# lab3_microprocessor.net
KiCad netlist of a schematic drawn in Altium Designer
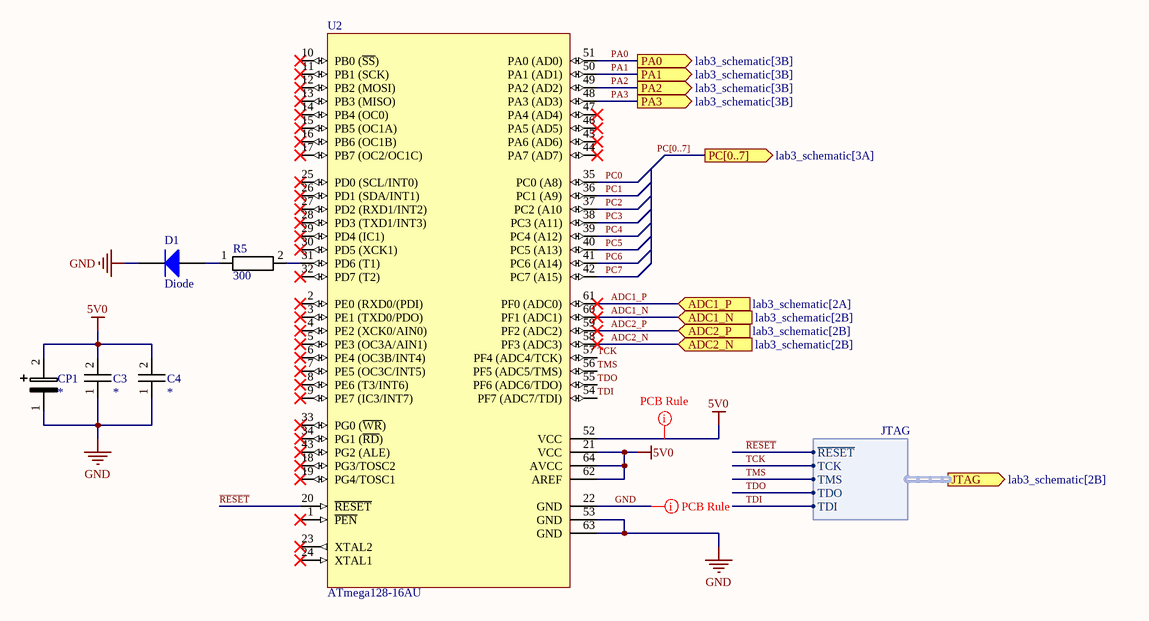
[diagram p0: lab3_microprocessor.SchDoc]

(export (version "E")
  (design (tool "Eeschema 10.0.6"))
  (components
    (comp (ref "C3")
      (value "*")
      (footprint "PcbLib_MW:0805_STD")
      (libsource (lib "Schlib_MW") (part "Capacitor"))
    )
    (comp (ref "C4")
      (value "*")
      (footprint "PcbLib_MW:0805_STD")
      (libsource (lib "Schlib_MW") (part "Capacitor"))
    )
    (comp (ref "CP1")
      (value "*")
      (footprint "PcbLib_MW:VJ_Tantalum_D")
      (libsource (lib "Schlib_MW") (part "Capacitor_polarized"))
    )
    (comp (ref "D1")
      (value "Diode")
      (footprint "SMC")
      (description "Default Diode")
      (fields (field (name "PUBLISHER") "Altium Limited"))
      (libsource (lib "Miscellaneous Devices") (part "Diode"))
    )
    (comp (ref "R5")
      (value "300")
      (footprint "PcbLib_MW:0603")
      (libsource (lib "Schlib_MW") (part "Resistor"))
    )
    (comp (ref "U2")
      (value "ATmega128-16AU")
      (footprint "PcbLib_MW:64A_M")
      (libsource (lib "Schlib_MW") (part "CMP-0095-00259-2"))
    )
  )
  (nets
    (net (code "2") (name "/ADC1_N") (class "Default")
      (node (ref "U2") (pin "60") (pinfunction "PF1_(ADC1)_60") (pintype "bidirectional+no_connect"))
    )
    (net (code "3") (name "/ADC1_P") (class "Default")
      (node (ref "U2") (pin "61") (pinfunction "PF0_(ADC0)_61") (pintype "bidirectional+no_connect"))
    )
    (net (code "4") (name "/ADC2_N") (class "Default")
      (node (ref "U2") (pin "58") (pinfunction "PF3_(ADC3)_58") (pintype "bidirectional+no_connect"))
    )
    (net (code "5") (name "/ADC2_P") (class "Default")
      (node (ref "U2") (pin "59") (pinfunction "PF2_(ADC2)_59") (pintype "bidirectional+no_connect"))
    )
    (net (code "6") (name "/PA0") (class "Default")
      (node (ref "U2") (pin "51") (pinfunction "PA0_(AD0)_51") (pintype "bidirectional"))
    )
    (net (code "7") (name "/PA1") (class "Default")
      (node (ref "U2") (pin "50") (pinfunction "PA1_(AD1)_50") (pintype "bidirectional"))
    )
    (net (code "8") (name "/PA2") (class "Default")
      (node (ref "U2") (pin "49") (pinfunction "PA2_(AD2)_49") (pintype "bidirectional"))
    )
    (net (code "9") (name "/PA3") (class "Default")
      (node (ref "U2") (pin "48") (pinfunction "PA3_(AD3)_48") (pintype "bidirectional"))
    )
    (net (code "10") (name "/PC0") (class "Default")
      (node (ref "U2") (pin "35") (pinfunction "PC0_(A8)_35") (pintype "bidirectional"))
    )
    (net (code "11") (name "/PC1") (class "Default")
      (node (ref "U2") (pin "36") (pinfunction "PC1_(A9)_36") (pintype "bidirectional"))
    )
    (net (code "12") (name "/PC2") (class "Default")
      (node (ref "U2") (pin "37") (pinfunction "PC2_(A10_37") (pintype "bidirectional"))
    )
    (net (code "13") (name "/PC3") (class "Default")
      (node (ref "U2") (pin "38") (pinfunction "PC3_(A11)_38") (pintype "bidirectional"))
    )
    (net (code "14") (name "/PC4") (class "Default")
      (node (ref "U2") (pin "39") (pinfunction "PC4_(A12)_39") (pintype "bidirectional"))
    )
    (net (code "15") (name "/PC5") (class "Default")
      (node (ref "U2") (pin "40") (pinfunction "PC5_(A13)_40") (pintype "bidirectional"))
    )
    (net (code "16") (name "/PC6") (class "Default")
      (node (ref "U2") (pin "41") (pinfunction "PC6_(A14)_41") (pintype "bidirectional"))
    )
    (net (code "17") (name "/PC7") (class "Default")
      (node (ref "U2") (pin "42") (pinfunction "PC7_(A15)_42") (pintype "bidirectional"))
    )
    (net (code "19") (name "/TCK") (class "Default")
      (node (ref "U2") (pin "57") (pinfunction "PF4_(ADC4/TCK)_57") (pintype "bidirectional"))
    )
    (net (code "20") (name "/TDI") (class "Default")
      (node (ref "U2") (pin "54") (pinfunction "PF7_(ADC7/TDI)_54") (pintype "bidirectional"))
    )
    (net (code "21") (name "/TDO") (class "Default")
      (node (ref "U2") (pin "55") (pinfunction "PF6_(ADC6/TDO)_55") (pintype "bidirectional"))
    )
    (net (code "22") (name "/TMS") (class "Default")
      (node (ref "U2") (pin "56") (pinfunction "PF5_(ADC5/TMS)_56") (pintype "bidirectional"))
    )
    (net (code "24") (name "/~{RESET}") (class "Default")
      (node (ref "U2") (pin "20") (pinfunction "~{RESET}_20") (pintype "input"))
    )
    (net (code "25") (name "5V0") (class "Default")
      (node (ref "C3") (pin "2") (pinfunction "PIN_2") (pintype "passive"))
      (node (ref "C4") (pin "2") (pinfunction "PIN_2") (pintype "passive"))
      (node (ref "CP1") (pin "2") (pinfunction "PIN_2") (pintype "passive"))
      (node (ref "U2") (pin "21") (pinfunction "VCC_21") (pintype "power_in"))
      (node (ref "U2") (pin "52") (pinfunction "VCC_52") (pintype "power_in"))
      (node (ref "U2") (pin "62") (pinfunction "AREF_62") (pintype "passive"))
      (node (ref "U2") (pin "64") (pinfunction "AVCC_64") (pintype "power_in"))
    )
    (net (code "26") (name "GND") (class "Default")
      (node (ref "C3") (pin "1") (pinfunction "PIN_1") (pintype "passive"))
      (node (ref "C4") (pin "1") (pinfunction "PIN_1") (pintype "passive"))
      (node (ref "CP1") (pin "1") (pinfunction "PIN_1") (pintype "passive"))
      (node (ref "D1") (pin "2") (pinfunction "K_2") (pintype "passive"))
      (node (ref "U2") (pin "22") (pinfunction "GND_22") (pintype "power_in"))
      (node (ref "U2") (pin "53") (pinfunction "GND_53") (pintype "power_in"))
      (node (ref "U2") (pin "63") (pinfunction "GND_63") (pintype "power_in"))
    )
    (net (code "27") (name "Net-(D1-A)") (class "Default")
      (node (ref "D1") (pin "1") (pinfunction "A_1") (pintype "passive"))
      (node (ref "R5") (pin "1") (pinfunction "PIN_1") (pintype "passive"))
    )
    (net (code "28") (name "Net-(U2-PD6_(T1))") (class "Default")
      (node (ref "R5") (pin "2") (pinfunction "PIN_2") (pintype "passive"))
      (node (ref "U2") (pin "31") (pinfunction "PD6_(T1)_31") (pintype "bidirectional"))
    )
    (net (code "29") (name "unconnected-(U2-PA4_(AD4)-Pad47)") (class "Default")
      (node (ref "U2") (pin "47") (pinfunction "PA4_(AD4)_47") (pintype "bidirectional+no_connect"))
    )
    (net (code "30") (name "unconnected-(U2-PA5_(AD5)-Pad46)") (class "Default")
      (node (ref "U2") (pin "46") (pinfunction "PA5_(AD5)_46") (pintype "bidirectional+no_connect"))
    )
    (net (code "31") (name "unconnected-(U2-PA6_(AD6)-Pad45)") (class "Default")
      (node (ref "U2") (pin "45") (pinfunction "PA6_(AD6)_45") (pintype "bidirectional+no_connect"))
    )
    (net (code "32") (name "unconnected-(U2-PA7_(AD7)-Pad44)") (class "Default")
      (node (ref "U2") (pin "44") (pinfunction "PA7_(AD7)_44") (pintype "bidirectional+no_connect"))
    )
    (net (code "33") (name "unconnected-(U2-PB0_(~{SS})-Pad10)") (class "Default")
      (node (ref "U2") (pin "10") (pinfunction "PB0_(~{SS})_10") (pintype "bidirectional+no_connect"))
    )
    (net (code "34") (name "unconnected-(U2-PB1_(SCK)-Pad11)") (class "Default")
      (node (ref "U2") (pin "11") (pinfunction "PB1_(SCK)_11") (pintype "bidirectional+no_connect"))
    )
    (net (code "35") (name "unconnected-(U2-PB2_(MOSI)-Pad12)") (class "Default")
      (node (ref "U2") (pin "12") (pinfunction "PB2_(MOSI)_12") (pintype "bidirectional+no_connect"))
    )
    (net (code "36") (name "unconnected-(U2-PB3_(MISO)-Pad13)") (class "Default")
      (node (ref "U2") (pin "13") (pinfunction "PB3_(MISO)_13") (pintype "bidirectional+no_connect"))
    )
    (net (code "37") (name "unconnected-(U2-PB4_(OC0)-Pad14)") (class "Default")
      (node (ref "U2") (pin "14") (pinfunction "PB4_(OC0)_14") (pintype "bidirectional+no_connect"))
    )
    (net (code "38") (name "unconnected-(U2-PB5_(OC1A)-Pad15)") (class "Default")
      (node (ref "U2") (pin "15") (pinfunction "PB5_(OC1A)_15") (pintype "bidirectional+no_connect"))
    )
    (net (code "39") (name "unconnected-(U2-PB6_(OC1B)-Pad16)") (class "Default")
      (node (ref "U2") (pin "16") (pinfunction "PB6_(OC1B)_16") (pintype "bidirectional+no_connect"))
    )
    (net (code "40") (name "unconnected-(U2-PB7_(OC2{slash}OC1C)-Pad17)") (class "Default")
      (node (ref "U2") (pin "17") (pinfunction "PB7_(OC2/OC1C)_17") (pintype "bidirectional+no_connect"))
    )
    (net (code "41") (name "unconnected-(U2-PD0_(SCL{slash}INT0)-Pad25)") (class "Default")
      (node (ref "U2") (pin "25") (pinfunction "PD0_(SCL/INT0)_25") (pintype "bidirectional+no_connect"))
    )
    (net (code "42") (name "unconnected-(U2-PD1_(SDA{slash}INT1)-Pad26)") (class "Default")
      (node (ref "U2") (pin "26") (pinfunction "PD1_(SDA/INT1)_26") (pintype "bidirectional+no_connect"))
    )
    (net (code "43") (name "unconnected-(U2-PD2_(RXD1{slash}INT2)-Pad27)") (class "Default")
      (node (ref "U2") (pin "27") (pinfunction "PD2_(RXD1/INT2)_27") (pintype "bidirectional+no_connect"))
    )
    (net (code "44") (name "unconnected-(U2-PD3_(TXD1{slash}INT3)-Pad28)") (class "Default")
      (node (ref "U2") (pin "28") (pinfunction "PD3_(TXD1/INT3)_28") (pintype "bidirectional+no_connect"))
    )
    (net (code "45") (name "unconnected-(U2-PD4_(IC1)-Pad29)") (class "Default")
      (node (ref "U2") (pin "29") (pinfunction "PD4_(IC1)_29") (pintype "bidirectional+no_connect"))
    )
    (net (code "46") (name "unconnected-(U2-PD5_(XCK1)-Pad30)") (class "Default")
      (node (ref "U2") (pin "30") (pinfunction "PD5_(XCK1)_30") (pintype "bidirectional+no_connect"))
    )
    (net (code "47") (name "unconnected-(U2-PD7_(T2)-Pad32)") (class "Default")
      (node (ref "U2") (pin "32") (pinfunction "PD7_(T2)_32") (pintype "bidirectional+no_connect"))
    )
    (net (code "48") (name "unconnected-(U2-PE0_(RXD0{slash}(PDI)-Pad2)") (class "Default")
      (node (ref "U2") (pin "2") (pinfunction "PE0_(RXD0/(PDI)_2") (pintype "bidirectional+no_connect"))
    )
    (net (code "49") (name "unconnected-(U2-PE1_(TXD0{slash}PDO)-Pad3)") (class "Default")
      (node (ref "U2") (pin "3") (pinfunction "PE1_(TXD0/PDO)_3") (pintype "bidirectional+no_connect"))
    )
    (net (code "50") (name "unconnected-(U2-PE2_(XCK0{slash}AIN0)-Pad4)") (class "Default")
      (node (ref "U2") (pin "4") (pinfunction "PE2_(XCK0/AIN0)_4") (pintype "bidirectional+no_connect"))
    )
    (net (code "51") (name "unconnected-(U2-PE3_(OC3A{slash}AIN1)-Pad5)") (class "Default")
      (node (ref "U2") (pin "5") (pinfunction "PE3_(OC3A/AIN1)_5") (pintype "bidirectional+no_connect"))
    )
    (net (code "52") (name "unconnected-(U2-PE4_(OC3B{slash}INT4)-Pad6)") (class "Default")
      (node (ref "U2") (pin "6") (pinfunction "PE4_(OC3B/INT4)_6") (pintype "bidirectional+no_connect"))
    )
    (net (code "53") (name "unconnected-(U2-PE5_(OC3C{slash}INT5)-Pad7)") (class "Default")
      (node (ref "U2") (pin "7") (pinfunction "PE5_(OC3C/INT5)_7") (pintype "bidirectional+no_connect"))
    )
    (net (code "54") (name "unconnected-(U2-PE6_(T3{slash}INT6)-Pad8)") (class "Default")
      (node (ref "U2") (pin "8") (pinfunction "PE6_(T3/INT6)_8") (pintype "bidirectional+no_connect"))
    )
    (net (code "55") (name "unconnected-(U2-PE7_(IC3{slash}INT7)-Pad9)") (class "Default")
      (node (ref "U2") (pin "9") (pinfunction "PE7_(IC3/INT7)_9") (pintype "bidirectional+no_connect"))
    )
    (net (code "56") (name "unconnected-(U2-PG0_(~{WR})-Pad33)") (class "Default")
      (node (ref "U2") (pin "33") (pinfunction "PG0_(~{WR})_33") (pintype "bidirectional+no_connect"))
    )
    (net (code "57") (name "unconnected-(U2-PG1_(~{RD})-Pad34)") (class "Default")
      (node (ref "U2") (pin "34") (pinfunction "PG1_(~{RD})_34") (pintype "bidirectional+no_connect"))
    )
    (net (code "58") (name "unconnected-(U2-PG2_(ALE)-Pad43)") (class "Default")
      (node (ref "U2") (pin "43") (pinfunction "PG2_(ALE)_43") (pintype "bidirectional+no_connect"))
    )
    (net (code "59") (name "unconnected-(U2-PG3{slash}TOSC2-Pad18)") (class "Default")
      (node (ref "U2") (pin "18") (pinfunction "PG3/TOSC2_18") (pintype "bidirectional+no_connect"))
    )
    (net (code "60") (name "unconnected-(U2-PG4{slash}TOSC1-Pad19)") (class "Default")
      (node (ref "U2") (pin "19") (pinfunction "PG4/TOSC1_19") (pintype "bidirectional+no_connect"))
    )
    (net (code "61") (name "unconnected-(U2-XTAL1-Pad24)") (class "Default")
      (node (ref "U2") (pin "24") (pinfunction "XTAL1_24") (pintype "input+no_connect"))
    )
    (net (code "62") (name "unconnected-(U2-XTAL2-Pad23)") (class "Default")
      (node (ref "U2") (pin "23") (pinfunction "XTAL2_23") (pintype "output+no_connect"))
    )
    (net (code "63") (name "unconnected-(U2-~{PEN}-Pad1)") (class "Default")
      (node (ref "U2") (pin "1") (pinfunction "~{PEN}_1") (pintype "input+no_connect"))
    )
  )
)
